# esp8266_programmer.net
KiCad netlist of a schematic drawn in EAGLE
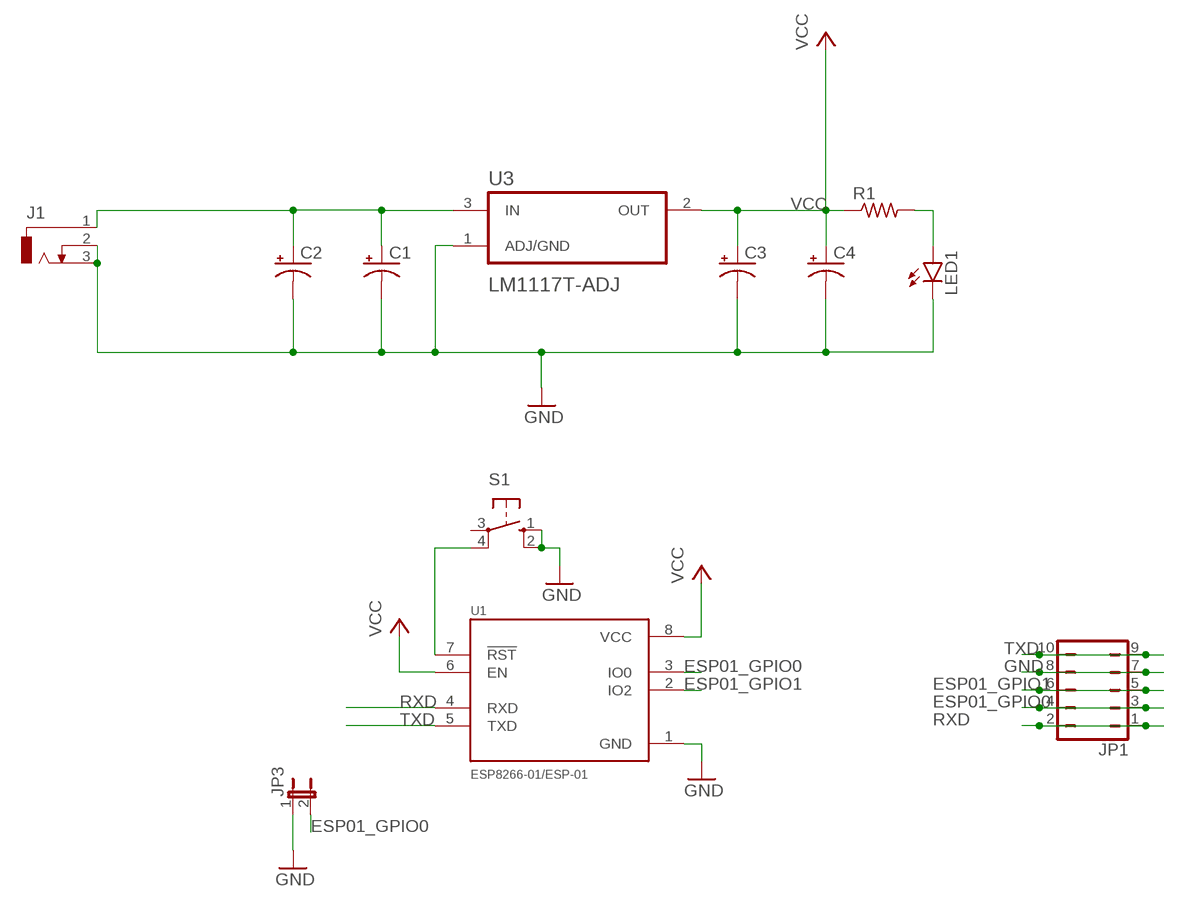
[diagram p0: schematic, sheet 1]

(export (version "E")
  (design (tool "Eeschema 10.0.6"))
  (components
    (comp (ref "C1")
      (value "CPOL-USE1.8-4")
      (footprint "eagle-import:E1,8-4")
      (libsource (lib "eagle-import") (part "CPOL-USE1.8-4"))
    )
    (comp (ref "C2")
      (value "CPOL-USE1.8-4")
      (footprint "eagle-import:E1,8-4")
      (libsource (lib "eagle-import") (part "CPOL-USE1.8-4"))
    )
    (comp (ref "C3")
      (value "CPOL-USE1.8-4")
      (footprint "eagle-import:E1,8-4")
      (libsource (lib "eagle-import") (part "CPOL-USE1.8-4"))
    )
    (comp (ref "C4")
      (value "CPOL-USE1.8-4")
      (footprint "eagle-import:E1,8-4")
      (libsource (lib "eagle-import") (part "CPOL-USE1.8-4"))
    )
    (comp (ref "J1")
      (value "DCJ0303")
      (footprint "eagle-import:DCJ0303")
      (libsource (lib "eagle-import") (part "DCJ0303"))
    )
    (comp (ref "JP1")
      (value "JP5Q")
      (footprint "eagle-import:JP5Q")
      (libsource (lib "eagle-import") (part "JP5Q"))
    )
    (comp (ref "JP3")
      (value "JP1E")
      (footprint "eagle-import:JP1")
      (libsource (lib "eagle-import") (part "JP1E"))
    )
    (comp (ref "LED1")
      (value "LED3MM")
      (footprint "eagle-import:LED3MM")
      (libsource (lib "eagle-import") (part "LED3MM"))
    )
    (comp (ref "R1")
      (value "R-US_0204/7")
      (footprint "eagle-import:0204_7")
      (libsource (lib "eagle-import") (part "R-US_0204/7"))
    )
    (comp (ref "S1")
      (value "10-XX")
      (footprint "eagle-import:B3F-10XX")
      (fields (field (name "MPN") "B3F-1000"))
      (libsource (lib "eagle-import") (part "10-XX"))
    )
    (comp (ref "U1")
      (value "ESP8266-01/ESP-01")
      (footprint "eagle-import:XCVR_ESP8266-01_ESP-01")
      (fields (field (name "MF") "AI-Thinker"))
      (libsource (lib "eagle-import") (part "ESP8266-01/ESP-01"))
    )
    (comp (ref "U3")
      (value "LM1117T-ADJ")
      (footprint "eagle-import:TO254P1054X470X1955-3")
      (fields (field (name "MF") "Texas Instruments"))
      (libsource (lib "eagle-import") (part "LM1117T-ADJ"))
    )
  )
  (nets
    (net (code "1") (name "/ESP01_GPIO0") (class "Default")
      (node (ref "JP1") (pin "3") (pinfunction "3_3") (pintype "passive"))
      (node (ref "JP1") (pin "4") (pinfunction "4_4") (pintype "passive"))
      (node (ref "JP3") (pin "2") (pinfunction "2_2") (pintype "passive"))
      (node (ref "U1") (pin "3") (pinfunction "IO0_3") (pintype "bidirectional"))
    )
    (net (code "2") (name "/ESP01_GPIO1") (class "Default")
      (node (ref "JP1") (pin "5") (pinfunction "5_5") (pintype "passive"))
      (node (ref "JP1") (pin "6") (pinfunction "6_6") (pintype "passive"))
      (node (ref "U1") (pin "2") (pinfunction "IO2_2") (pintype "bidirectional"))
    )
    (net (code "3") (name "/RXD") (class "Default")
      (node (ref "JP1") (pin "1") (pinfunction "1_1") (pintype "passive"))
      (node (ref "JP1") (pin "2") (pinfunction "2_2") (pintype "passive"))
      (node (ref "U1") (pin "4") (pinfunction "RXD_4") (pintype "input"))
    )
    (net (code "4") (name "/TXD") (class "Default")
      (node (ref "JP1") (pin "10") (pinfunction "10_10") (pintype "passive"))
      (node (ref "JP1") (pin "9") (pinfunction "9_9") (pintype "passive"))
      (node (ref "U1") (pin "5") (pinfunction "TXD_5") (pintype "output"))
    )
    (net (code "5") (name "GND") (class "Default")
      (node (ref "C1") (pin "-") (pinfunction "-_-") (pintype "passive"))
      (node (ref "C2") (pin "-") (pinfunction "-_-") (pintype "passive"))
      (node (ref "C3") (pin "-") (pinfunction "-_-") (pintype "passive"))
      (node (ref "C4") (pin "-") (pinfunction "-_-") (pintype "passive"))
      (node (ref "J1") (pin "2") (pinfunction "2_2") (pintype "passive"))
      (node (ref "J1") (pin "3") (pinfunction "3_3") (pintype "passive"))
      (node (ref "JP1") (pin "7") (pinfunction "7_7") (pintype "passive"))
      (node (ref "JP1") (pin "8") (pinfunction "8_8") (pintype "passive"))
      (node (ref "JP3") (pin "1") (pinfunction "1_1") (pintype "passive"))
      (node (ref "LED1") (pin "K") (pinfunction "C_K") (pintype "passive"))
      (node (ref "S1") (pin "1") (pinfunction "S_1") (pintype "passive"))
      (node (ref "S1") (pin "2") (pinfunction "S1_2") (pintype "passive"))
      (node (ref "U1") (pin "1") (pinfunction "GND_1") (pintype "power_in"))
      (node (ref "U3") (pin "1") (pinfunction "ADJ/GND_1") (pintype "bidirectional"))
    )
    (net (code "6") (name "Net-(LED1-PadA)") (class "Default")
      (node (ref "LED1") (pin "A") (pinfunction "A_A") (pintype "passive"))
      (node (ref "R1") (pin "2") (pinfunction "2_2") (pintype "passive"))
    )
    (net (code "7") (name "Net-(S1-P1)") (class "Default")
      (node (ref "S1") (pin "4") (pinfunction "P1_4") (pintype "passive"))
      (node (ref "U1") (pin "7") (pinfunction "~{RST}_7") (pintype "input"))
    )
    (net (code "8") (name "Net-(U3-IN)") (class "Default")
      (node (ref "C1") (pin "+") (pinfunction "+_+") (pintype "passive"))
      (node (ref "C2") (pin "+") (pinfunction "+_+") (pintype "passive"))
      (node (ref "J1") (pin "1") (pinfunction "1_1") (pintype "passive"))
      (node (ref "U3") (pin "3") (pinfunction "IN_3") (pintype "input"))
    )
    (net (code "9") (name "VCC") (class "Default")
      (node (ref "C3") (pin "+") (pinfunction "+_+") (pintype "passive"))
      (node (ref "C4") (pin "+") (pinfunction "+_+") (pintype "passive"))
      (node (ref "R1") (pin "1") (pinfunction "1_1") (pintype "passive"))
      (node (ref "U1") (pin "6") (pinfunction "EN_6") (pintype "input"))
      (node (ref "U1") (pin "8") (pinfunction "VCC_8") (pintype "power_in"))
      (node (ref "U3") (pin "2") (pinfunction "OUT_2") (pintype "output"))
    )
    (net (code "10") (name "unconnected-(S1-P-Pad3)") (class "Default")
      (node (ref "S1") (pin "3") (pinfunction "P_3") (pintype "passive"))
    )
  )
)
